# Display_Mux.net
KiCad netlist of a schematic drawn in Altium Designer
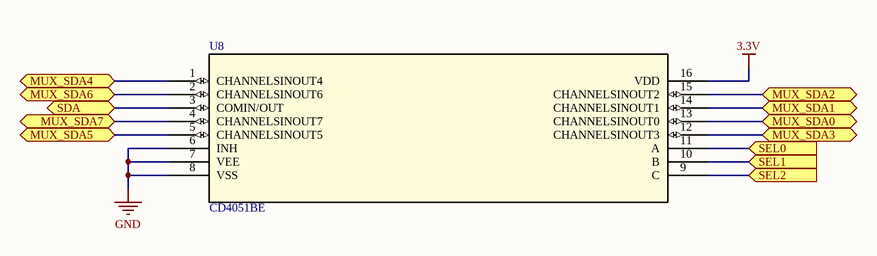
[diagram p0: Display_Mux.SchDoc]

(export (version "E")
  (design (tool "Eeschema 10.0.6"))
  (components
    (comp (ref "U8")
      (value "CD4051BE")
      (footprint "N16")
      (description "Imported")
      (fields
        (field (name "RS_PART_NUMBER") "5036098")
        (field (name "COPYRIGHT") "Copyright (C) 2015 Accelerated Designs. All rights reserved")
      )
      (libsource (lib "display_mux") (part "CD4051BE"))
    )
  )
  (nets
    (net (code "1") (name "/MUX_SDA0") (class "Default")
      (node (ref "U8") (pin "13") (pinfunction "CHANNELSINOUT0_13") (pintype "bidirectional"))
    )
    (net (code "2") (name "/MUX_SDA1") (class "Default")
      (node (ref "U8") (pin "14") (pinfunction "CHANNELSINOUT1_14") (pintype "bidirectional"))
    )
    (net (code "3") (name "/MUX_SDA2") (class "Default")
      (node (ref "U8") (pin "15") (pinfunction "CHANNELSINOUT2_15") (pintype "bidirectional"))
    )
    (net (code "4") (name "/MUX_SDA3") (class "Default")
      (node (ref "U8") (pin "12") (pinfunction "CHANNELSINOUT3_12") (pintype "bidirectional"))
    )
    (net (code "5") (name "/MUX_SDA4") (class "Default")
      (node (ref "U8") (pin "1") (pinfunction "CHANNELSINOUT4_1") (pintype "bidirectional"))
    )
    (net (code "6") (name "/MUX_SDA5") (class "Default")
      (node (ref "U8") (pin "5") (pinfunction "CHANNELSINOUT5_5") (pintype "bidirectional"))
    )
    (net (code "7") (name "/MUX_SDA6") (class "Default")
      (node (ref "U8") (pin "2") (pinfunction "CHANNELSINOUT6_2") (pintype "bidirectional"))
    )
    (net (code "8") (name "/MUX_SDA7") (class "Default")
      (node (ref "U8") (pin "4") (pinfunction "CHANNELSINOUT7_4") (pintype "bidirectional"))
    )
    (net (code "9") (name "/SDA") (class "Default")
      (node (ref "U8") (pin "3") (pinfunction "COMIN/OUT_3") (pintype "bidirectional"))
    )
    (net (code "10") (name "/SEL0") (class "Default")
      (node (ref "U8") (pin "11") (pinfunction "A_11") (pintype "passive"))
    )
    (net (code "11") (name "/SEL1") (class "Default")
      (node (ref "U8") (pin "10") (pinfunction "B_10") (pintype "passive"))
    )
    (net (code "12") (name "/SEL2") (class "Default")
      (node (ref "U8") (pin "9") (pinfunction "C_9") (pintype "passive"))
    )
    (net (code "13") (name "3.3V") (class "Default")
      (node (ref "U8") (pin "16") (pinfunction "VDD_16") (pintype "power_in"))
    )
    (net (code "14") (name "GND") (class "Default")
      (node (ref "U8") (pin "6") (pinfunction "INH_6") (pintype "passive"))
      (node (ref "U8") (pin "7") (pinfunction "VEE_7") (pintype "power_in"))
      (node (ref "U8") (pin "8") (pinfunction "VSS_8") (pintype "power_in"))
    )
  )
)
